# Miscellaneous.net
KiCad netlist of a schematic drawn in Altium Designer
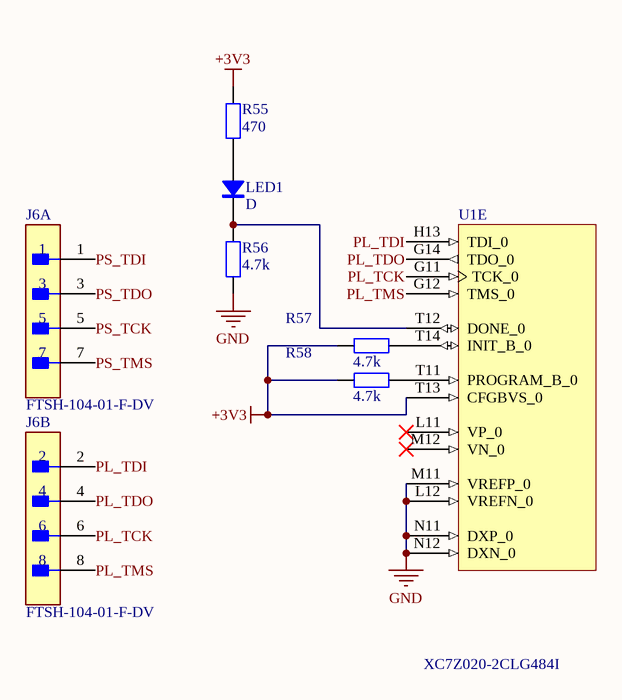
[diagram p0: Miscellaneous.SchDoc]

(export (version "E")
  (design (tool "Eeschema 10.0.6"))
  (components
    (comp (ref "J6")
      (value "FTSH-104-01-F-DV")
      (footprint "FP-FTSH-104-01-F-DV-MFG")
      (description "CONN HEADER SMD 8POS 1.27MM")
      (libsource (lib "Altium Content Vault") (part "811e954b9c034aa737de4d9295cbe7e"))
    )
    (comp (ref "LED1") (value "D") (footprint "R0603") (libsource (lib "Passive") (part "D")))
    (comp (ref "R55") (value "470") (footprint "R0402") (libsource (lib "Passive") (part "R")))
    (comp (ref "R56") (value "4.7k") (footprint "R0402") (libsource (lib "Passive") (part "R")))
    (comp (ref "R57") (value "4.7k") (footprint "R0402") (libsource (lib "Passive") (part "R")))
    (comp (ref "R58") (value "4.7k") (footprint "R0402") (libsource (lib "Passive") (part "R")))
    (comp (ref "U1")
      (value "XC7Z020-2CLG484I")
      (footprint "CLG484")
      (fields (field (name "GENERIC PART NUMBER") "XC7Z020"))
      (libsource (lib "Altium Content Vault") (part "XNLX-XC7Z020-CLG484"))
    )
  )
  (nets
    (net (code "1") (name "+3V3") (class "Default")
      (node (ref "R55") (pin "1") (pinfunction "1_1") (pintype "passive"))
      (node (ref "R57") (pin "1") (pinfunction "1_1") (pintype "passive"))
      (node (ref "R58") (pin "1") (pinfunction "1_1") (pintype "passive"))
      (node (ref "U1") (pin "T13") (pinfunction "CFGBVS_0_T13") (pintype "input"))
    )
    (net (code "2") (name "/PL_TCK") (class "Default")
      (node (ref "J6") (pin "6") (pinfunction "6_6") (pintype "passive"))
      (node (ref "U1") (pin "G11") (pinfunction "TCK_0_G11") (pintype "input"))
    )
    (net (code "3") (name "/PL_TDI") (class "Default")
      (node (ref "J6") (pin "2") (pinfunction "2_2") (pintype "passive"))
      (node (ref "U1") (pin "H13") (pinfunction "TDI_0_H13") (pintype "input"))
    )
    (net (code "4") (name "/PL_TDO") (class "Default")
      (node (ref "J6") (pin "4") (pinfunction "4_4") (pintype "passive"))
      (node (ref "U1") (pin "G14") (pinfunction "TDO_0_G14") (pintype "output"))
    )
    (net (code "5") (name "/PL_TMS") (class "Default")
      (node (ref "J6") (pin "8") (pinfunction "8_8") (pintype "passive"))
      (node (ref "U1") (pin "G12") (pinfunction "TMS_0_G12") (pintype "input"))
    )
    (net (code "6") (name "/PS_TCK") (class "Default")
      (node (ref "J6") (pin "5") (pinfunction "5_5") (pintype "passive"))
    )
    (net (code "7") (name "/PS_TDI") (class "Default")
      (node (ref "J6") (pin "1") (pinfunction "1_1") (pintype "passive"))
    )
    (net (code "8") (name "/PS_TDO") (class "Default")
      (node (ref "J6") (pin "3") (pinfunction "3_3") (pintype "passive"))
    )
    (net (code "9") (name "/PS_TMS") (class "Default")
      (node (ref "J6") (pin "7") (pinfunction "7_7") (pintype "passive"))
    )
    (net (code "10") (name "GND") (class "Default")
      (node (ref "R56") (pin "2") (pinfunction "2_2") (pintype "passive"))
      (node (ref "U1") (pin "L12") (pinfunction "VREFN_0_L12") (pintype "input"))
      (node (ref "U1") (pin "M11") (pinfunction "VREFP_0_M11") (pintype "input"))
      (node (ref "U1") (pin "N11") (pinfunction "DXP_0_N11") (pintype "input"))
      (node (ref "U1") (pin "N12") (pinfunction "DXN_0_N12") (pintype "input"))
    )
    (net (code "11") (name "Net-(LED1-A)") (class "Default")
      (node (ref "LED1") (pin "1") (pinfunction "A_1") (pintype "passive"))
      (node (ref "R55") (pin "2") (pinfunction "2_2") (pintype "passive"))
    )
    (net (code "12") (name "Net-(LED1-K)") (class "Default")
      (node (ref "LED1") (pin "2") (pinfunction "K_2") (pintype "passive"))
      (node (ref "R56") (pin "1") (pinfunction "1_1") (pintype "passive"))
      (node (ref "U1") (pin "T12") (pinfunction "DONE_0_T12") (pintype "bidirectional"))
    )
    (net (code "13") (name "Net-(U1E-INIT_B_0)") (class "Default")
      (node (ref "R57") (pin "2") (pinfunction "2_2") (pintype "passive"))
      (node (ref "U1") (pin "T14") (pinfunction "INIT_B_0_T14") (pintype "bidirectional"))
    )
    (net (code "14") (name "Net-(U1E-PROGRAM_B_0)") (class "Default")
      (node (ref "R58") (pin "2") (pinfunction "2_2") (pintype "passive"))
      (node (ref "U1") (pin "T11") (pinfunction "PROGRAM_B_0_T11") (pintype "input"))
    )
    (net (code "15") (name "unconnected-(U1E-VN_0-PadM12)") (class "Default")
      (node (ref "U1") (pin "M12") (pinfunction "VN_0_M12") (pintype "input+no_connect"))
    )
    (net (code "16") (name "unconnected-(U1E-VP_0-PadL11)") (class "Default")
      (node (ref "U1") (pin "L11") (pinfunction "VP_0_L11") (pintype "input+no_connect"))
    )
  )
)
